# MCU.net
KiCad netlist of a schematic drawn in Altium Designer
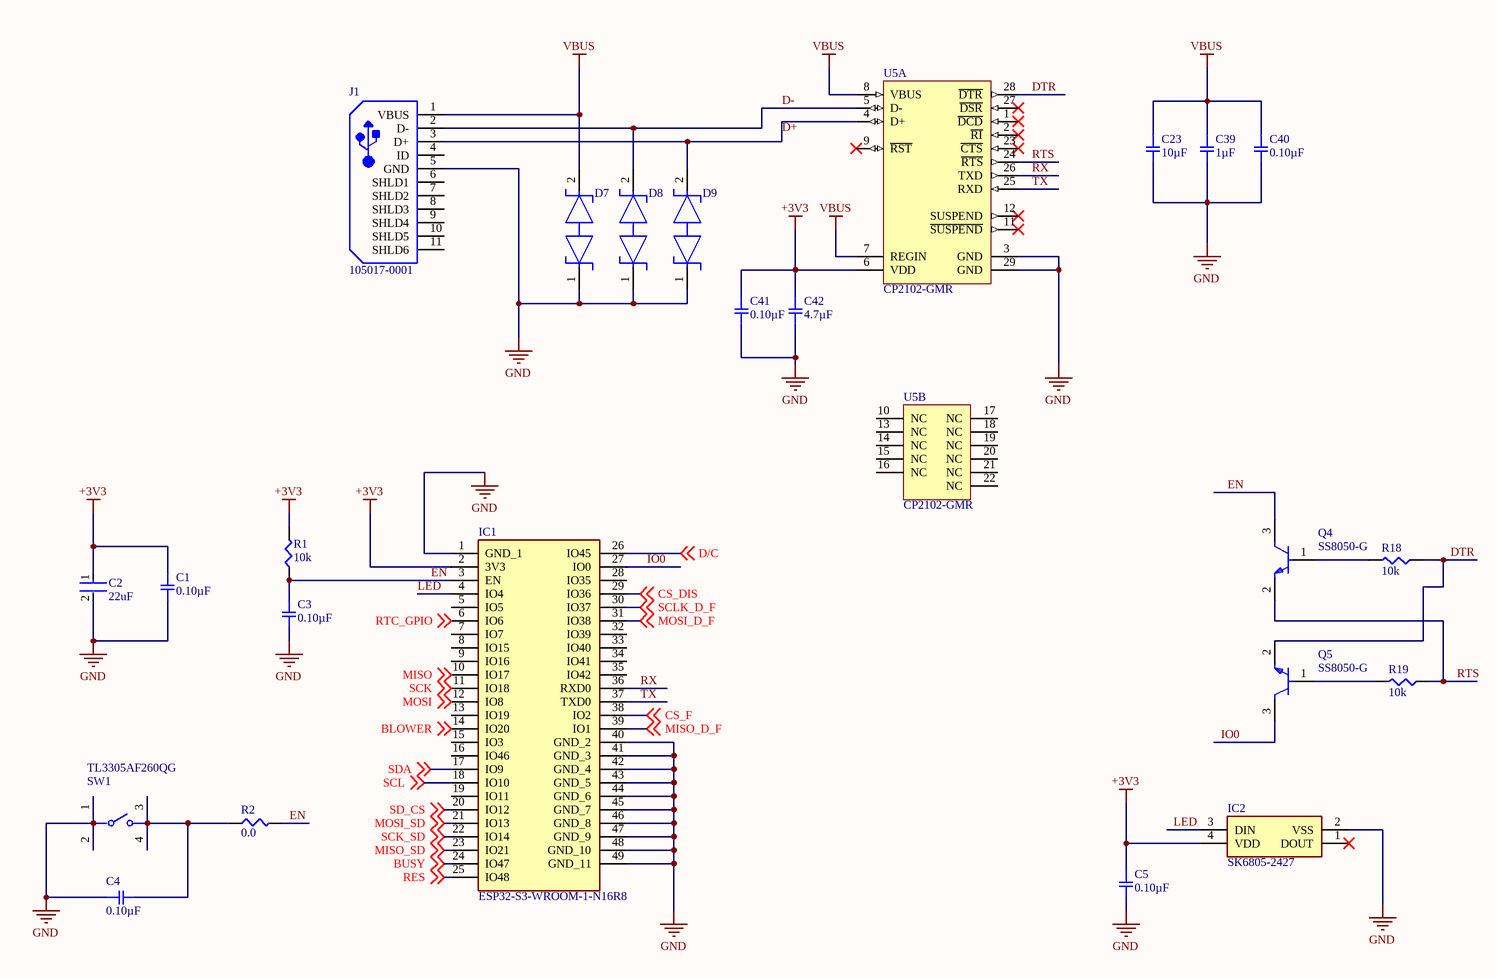
[diagram p0: MCU.SchDoc]

(export (version "E")
  (design (tool "Eeschema 10.0.6"))
  (components
    (comp (ref "C1")
      (value "0.10µF")
      (footprint "SMD-0402C")
      (description "CAP CER 0.1UF 16V X7R 0402")
      (fields
        (field (name "DIGI-KEY PART NUMBER") "490-4759-1-ND")
        (field (name "PART NUMBER") "GCM155R71C104KA55D")
      )
      (libsource (lib "capacitor_murata_0402") (part "GCM155R71C104KA55D"))
    )
    (comp (ref "C2")
      (value "22uF")
      (footprint "FP-CL05A226MQ5N6J8-IPC_C")
      (description "CAP CER 22UF 6.3V X5R 0402")
      (fields
        (field (name "MANUFACTURER PART NUMBER") "CL05A226MQ5N6J8")
        (field (name "MANUFACTURER") "Samsung Electro-Mechanics")
      )
      (libsource (lib "Altium Content Vault") (part "11868f565c42a9108669ba33697ecf6"))
    )
    (comp (ref "C3")
      (value "0.10µF")
      (footprint "SMD-0402C")
      (description "CAP CER 0.1UF 16V X7R 0402")
      (fields
        (field (name "DIGI-KEY PART NUMBER") "490-4759-1-ND")
        (field (name "PART NUMBER") "GCM155R71C104KA55D")
      )
      (libsource (lib "capacitor_murata_0402") (part "GCM155R71C104KA55D"))
    )
    (comp (ref "C4")
      (value "0.10µF")
      (footprint "SMD-0402C")
      (description "CAP CER 0.1UF 16V X7R 0402")
      (fields
        (field (name "DIGI-KEY PART NUMBER") "490-4759-1-ND")
        (field (name "PART NUMBER") "GCM155R71C104KA55D")
      )
      (libsource (lib "capacitor_murata_0402") (part "GCM155R71C104KA55D"))
    )
    (comp (ref "C5")
      (value "0.10µF")
      (footprint "SMD-0402C")
      (description "CAP CER 0.1UF 16V X7R 0402")
      (fields
        (field (name "DIGI-KEY PART NUMBER") "490-4759-1-ND")
        (field (name "PART NUMBER") "GCM155R71C104KA55D")
      )
      (libsource (lib "capacitor_murata_0402") (part "GCM155R71C104KA55D"))
    )
    (comp (ref "C23")
      (value "10µF")
      (footprint "SMD-0402C")
      (description "CAP CER 10UF 6.3V X5R 0402")
      (fields
        (field (name "DIGI-KEY PART NUMBER") "490-13251-1-ND")
        (field (name "PART NUMBER") "ZRB15XR60J106ME12D")
      )
      (libsource (lib "capacitor_murata_0402") (part "ZRB15XR60J106ME12D"))
    )
    (comp (ref "C39")
      (value "1µF")
      (footprint "SMD-0402C")
      (description "CAP CER 1UF 10V X7S 0402")
      (fields
        (field (name "DIGI-KEY PART NUMBER") "490-13409-1-ND")
        (field (name "PART NUMBER") "GCM155C71A105KE38D")
      )
      (libsource (lib "capacitor_murata_0402") (part "GCM155C71A105KE38D"))
    )
    (comp (ref "C40")
      (value "0.10µF")
      (footprint "SMD-0402C")
      (description "CAP CER 0.1UF 16V X7R 0402")
      (fields
        (field (name "DIGI-KEY PART NUMBER") "490-4759-1-ND")
        (field (name "PART NUMBER") "GCM155R71C104KA55D")
      )
      (libsource (lib "capacitor_murata_0402") (part "GCM155R71C104KA55D"))
    )
    (comp (ref "C41")
      (value "0.10µF")
      (footprint "SMD-0402C")
      (description "CAP CER 0.1UF 16V X7R 0402")
      (fields
        (field (name "DIGI-KEY PART NUMBER") "490-4759-1-ND")
        (field (name "PART NUMBER") "GCM155R71C104KA55D")
      )
      (libsource (lib "capacitor_murata_0402") (part "GCM155R71C104KA55D"))
    )
    (comp (ref "C42")
      (value "4.7µF")
      (footprint "SMD-0402C")
      (description "CAP CER 4.7UF 10V X5R 0402")
      (fields
        (field (name "DIGI-KEY PART NUMBER") "490-13252-1-ND")
        (field (name "PART NUMBER") "ZRB15XR61A475KE01D")
      )
      (libsource (lib "capacitor_murata_0402") (part "ZRB15XR61A475KE01D"))
    )
    (comp (ref "D7")
      (value "PD1E10B06DPYR")
      (footprint "FP-DPY0002A-MFG")
      (description "TVS DIODE 5.5V 14V 2X1SON")
      (libsource (lib "Altium Content Vault") (part "208e19b57522434895fa003e5d5b197"))
    )
    (comp (ref "D8")
      (value "PD1E10B06DPYR")
      (footprint "FP-DPY0002A-MFG")
      (description "TVS DIODE 5.5V 14V 2X1SON")
      (libsource (lib "Altium Content Vault") (part "208e19b57522434895fa003e5d5b197"))
    )
    (comp (ref "D9")
      (value "PD1E10B06DPYR")
      (footprint "FP-DPY0002A-MFG")
      (description "TVS DIODE 5.5V 14V 2X1SON")
      (libsource (lib "Altium Content Vault") (part "208e19b57522434895fa003e5d5b197"))
    )
    (comp (ref "IC1")
      (value "ESP32-S3-WROOM-1-N16R8")
      (footprint "SamacSys:ESP32S3WROOM1N16R8")
      (description "Integrated Circuit")
      (fields (field (name "MOUSER PART NUMBER") "356-ESP32S3WRM1N16R8"))
      (libsource (lib "SamacSys") (part "ESP32-S3-WROOM-1-N16R8"))
    )
    (comp (ref "IC2")
      (value "SK6805-2427")
      (footprint "SamacSys:SK68052427")
      (description "Integrated Circuit")
      (libsource (lib "*") (part "SK6805-2427"))
    )
    (comp (ref "J1")
      (value "105017-0001")
      (footprint "USB-MICRO-B_V")
      (fields (field (name "MANUFACTURER") "Molex"))
      (libsource (lib "Altium Content Vault") (part "USB-5-6SHLD"))
    )
    (comp (ref "Q4")
      (value "SS8050-G")
      (footprint "FP-SS8050-G-MFG")
      (description "NPN TRANSISTOR 1.5A 40V SOT-23 R")
      (libsource (lib "Altium Content Vault") (part "2a1388f82443b098dcd57d24ac7632d"))
    )
    (comp (ref "Q5")
      (value "SS8050-G")
      (footprint "FP-SS8050-G-MFG")
      (description "NPN TRANSISTOR 1.5A 40V SOT-23 R")
      (libsource (lib "Altium Content Vault") (part "2a1388f82443b098dcd57d24ac7632d"))
    )
    (comp (ref "R1")
      (value "10k")
      (footprint "SMD-0402-RES")
      (description "RES SMD 10K OHM 5% 1/10W 0402")
      (fields (field (name "PART NUMBER") "ERJ-2GEJ103X") (field (name "DIGI-KEY PART NUMBER") "P10KJCT-ND"))
      (libsource (lib "Panasonic_ERJ_0402") (part "ERJ-2GEJ103X"))
    )
    (comp (ref "R2")
      (value "0.0")
      (footprint "SMD-0402-RES")
      (description "RES SMD 0.0OHM JUMPER 1/10W 0402")
      (fields (field (name "PART NUMBER") "ERJ-2GE0R00X") (field (name "DIGI-KEY PART NUMBER") "P0.0JCT-ND"))
      (libsource (lib "Panasonic_ERJ_0402") (part "ERJ-2GE0R00X"))
    )
    (comp (ref "R18")
      (value "10k")
      (footprint "SMD-0402-RES")
      (description "RES SMD 10K OHM 5% 1/10W 0402")
      (fields (field (name "PART NUMBER") "ERJ-2GEJ103X") (field (name "DIGI-KEY PART NUMBER") "P10KJCT-ND"))
      (libsource (lib "Panasonic_ERJ_0402") (part "ERJ-2GEJ103X"))
    )
    (comp (ref "R19")
      (value "10k")
      (footprint "SMD-0402-RES")
      (description "RES SMD 10K OHM 5% 1/10W 0402")
      (fields (field (name "PART NUMBER") "ERJ-2GEJ103X") (field (name "DIGI-KEY PART NUMBER") "P10KJCT-ND"))
      (libsource (lib "Panasonic_ERJ_0402") (part "ERJ-2GEJ103X"))
    )
    (comp (ref "SW1")
      (value "TL3305AF260QG")
      (footprint "FP-TL3305AF260QG-MFG")
      (description "SWITCH TACTILE SPST-NO 50MA 12V")
      (libsource (lib "Altium Content Vault") (part "b8895f3f4cefb76e1819d2863dba89b"))
    )
    (comp (ref "U5")
      (value "CP2102-GMR")
      (footprint "SLAB-QFN-28-3125x3125TP_M")
      (description "Single-Chip USB to URAT Bridge, 3.3 V, -40 to 85 degC, 28-Pin QFN, RoHS, Tape and Reel")
      (fields (field (name "MANUFACTURER") "Silicon Labs"))
      (libsource (lib "Altium Content Vault") (part "SLAB-CP210X-QFN-28-29"))
    )
  )
  (nets
    (net (code "1") (name "+3V3") (class "Default")
      (node (ref "C1") (pin "1") (pinfunction "1_1") (pintype "passive"))
      (node (ref "C2") (pin "1") (pinfunction "1_1") (pintype "passive"))
      (node (ref "C41") (pin "1") (pinfunction "1_1") (pintype "passive"))
      (node (ref "C42") (pin "1") (pinfunction "1_1") (pintype "passive"))
      (node (ref "C5") (pin "1") (pinfunction "1_1") (pintype "passive"))
      (node (ref "IC1") (pin "2") (pinfunction "3V3_2") (pintype "passive"))
      (node (ref "IC2") (pin "4") (pinfunction "VDD_4") (pintype "passive"))
      (node (ref "R1") (pin "2") (pinfunction "2_2") (pintype "passive"))
      (node (ref "U5") (pin "6") (pinfunction "VDD_6") (pintype "power_in"))
    )
    (net (code "2") (name "/D+") (class "Default")
      (node (ref "D9") (pin "2") (pinfunction "2_2") (pintype "passive"))
      (node (ref "J1") (pin "3") (pinfunction "D+_3") (pintype "passive"))
      (node (ref "U5") (pin "4") (pinfunction "D+_4") (pintype "bidirectional"))
    )
    (net (code "3") (name "/D-") (class "Default")
      (node (ref "D8") (pin "2") (pinfunction "2_2") (pintype "passive"))
      (node (ref "J1") (pin "2") (pinfunction "D-_2") (pintype "passive"))
      (node (ref "U5") (pin "5") (pinfunction "D-_5") (pintype "bidirectional"))
    )
    (net (code "4") (name "/DTR") (class "Default")
      (node (ref "Q5") (pin "2") (pinfunction "E_2") (pintype "passive"))
      (node (ref "R18") (pin "1") (pinfunction "1_1") (pintype "passive"))
      (node (ref "U5") (pin "28") (pinfunction "~{DTR}_28") (pintype "output"))
    )
    (net (code "5") (name "/EN") (class "Default")
      (node (ref "C3") (pin "1") (pinfunction "1_1") (pintype "passive"))
      (node (ref "IC1") (pin "3") (pinfunction "EN_3") (pintype "passive"))
      (node (ref "Q4") (pin "3") (pinfunction "C_3") (pintype "passive"))
      (node (ref "R1") (pin "1") (pinfunction "1_1") (pintype "passive"))
      (node (ref "R2") (pin "2") (pinfunction "2_2") (pintype "passive"))
    )
    (net (code "6") (name "/IO0") (class "Default")
      (node (ref "IC1") (pin "27") (pinfunction "IO0_27") (pintype "passive"))
      (node (ref "Q5") (pin "3") (pinfunction "C_3") (pintype "passive"))
    )
    (net (code "7") (name "/LED") (class "Default")
      (node (ref "IC1") (pin "4") (pinfunction "IO4_4") (pintype "passive"))
      (node (ref "IC2") (pin "3") (pinfunction "DIN_3") (pintype "passive"))
    )
    (net (code "8") (name "/RTS") (class "Default")
      (node (ref "Q4") (pin "2") (pinfunction "E_2") (pintype "passive"))
      (node (ref "R19") (pin "1") (pinfunction "1_1") (pintype "passive"))
      (node (ref "U5") (pin "24") (pinfunction "~{RTS}_24") (pintype "output"))
    )
    (net (code "9") (name "/RX") (class "Default")
      (node (ref "IC1") (pin "36") (pinfunction "RXD0_36") (pintype "passive"))
      (node (ref "U5") (pin "26") (pinfunction "TXD_26") (pintype "output"))
    )
    (net (code "10") (name "/TX") (class "Default")
      (node (ref "IC1") (pin "37") (pinfunction "TXD0_37") (pintype "passive"))
      (node (ref "U5") (pin "25") (pinfunction "RXD_25") (pintype "input"))
    )
    (net (code "11") (name "BLOWER") (class "Default")
      (node (ref "IC1") (pin "14") (pinfunction "IO20_14") (pintype "passive"))
    )
    (net (code "12") (name "BUSY") (class "Default")
      (node (ref "IC1") (pin "24") (pinfunction "IO47_24") (pintype "passive"))
    )
    (net (code "13") (name "CS_DIS") (class "Default")
      (node (ref "IC1") (pin "29") (pinfunction "IO36_29") (pintype "passive"))
    )
    (net (code "14") (name "CS_F") (class "Default")
      (node (ref "IC1") (pin "38") (pinfunction "IO2_38") (pintype "passive"))
    )
    (net (code "15") (name "D{slash}C") (class "Default")
      (node (ref "IC1") (pin "26") (pinfunction "IO45_26") (pintype "passive"))
    )
    (net (code "16") (name "GND") (class "Default")
      (node (ref "C1") (pin "2") (pinfunction "2_2") (pintype "passive"))
      (node (ref "C2") (pin "2") (pinfunction "2_2") (pintype "passive"))
      (node (ref "C23") (pin "2") (pinfunction "2_2") (pintype "passive"))
      (node (ref "C3") (pin "2") (pinfunction "2_2") (pintype "passive"))
      (node (ref "C39") (pin "2") (pinfunction "2_2") (pintype "passive"))
      (node (ref "C4") (pin "1") (pinfunction "1_1") (pintype "passive"))
      (node (ref "C40") (pin "2") (pinfunction "2_2") (pintype "passive"))
      (node (ref "C41") (pin "2") (pinfunction "2_2") (pintype "passive"))
      (node (ref "C42") (pin "2") (pinfunction "2_2") (pintype "passive"))
      (node (ref "C5") (pin "2") (pinfunction "2_2") (pintype "passive"))
      (node (ref "D7") (pin "1") (pinfunction "1_1") (pintype "passive"))
      (node (ref "D8") (pin "1") (pinfunction "1_1") (pintype "passive"))
      (node (ref "D9") (pin "1") (pinfunction "1_1") (pintype "passive"))
      (node (ref "IC1") (pin "1") (pinfunction "GND_1_1") (pintype "passive"))
      (node (ref "IC1") (pin "40") (pinfunction "GND_2_40") (pintype "passive"))
      (node (ref "IC1") (pin "41") (pinfunction "GND_3_41") (pintype "passive"))
      (node (ref "IC1") (pin "42") (pinfunction "GND_4_42") (pintype "passive"))
      (node (ref "IC1") (pin "43") (pinfunction "GND_5_43") (pintype "passive"))
      (node (ref "IC1") (pin "44") (pinfunction "GND_6_44") (pintype "passive"))
      (node (ref "IC1") (pin "45") (pinfunction "GND_7_45") (pintype "passive"))
      (node (ref "IC1") (pin "46") (pinfunction "GND_8_46") (pintype "passive"))
      (node (ref "IC1") (pin "47") (pinfunction "GND_9_47") (pintype "passive"))
      (node (ref "IC1") (pin "48") (pinfunction "GND_10_48") (pintype "passive"))
      (node (ref "IC1") (pin "49") (pinfunction "GND_11_49") (pintype "passive"))
      (node (ref "IC2") (pin "2") (pinfunction "VSS_2") (pintype "passive"))
      (node (ref "J1") (pin "5") (pinfunction "GND_5") (pintype "passive"))
      (node (ref "SW1") (pin "1") (pinfunction "1_1") (pintype "passive"))
      (node (ref "SW1") (pin "2") (pinfunction "2_2") (pintype "passive"))
      (node (ref "U5") (pin "29") (pinfunction "GND_29") (pintype "power_in"))
      (node (ref "U5") (pin "3") (pinfunction "GND_3") (pintype "power_in"))
    )
    (net (code "17") (name "MISO") (class "Default")
      (node (ref "IC1") (pin "10") (pinfunction "IO17_10") (pintype "passive"))
    )
    (net (code "18") (name "MISO_D_F") (class "Default")
      (node (ref "IC1") (pin "39") (pinfunction "IO1_39") (pintype "passive"))
    )
    (net (code "19") (name "MISO_SD") (class "Default")
      (node (ref "IC1") (pin "23") (pinfunction "IO21_23") (pintype "passive"))
    )
    (net (code "20") (name "MOSI") (class "Default")
      (node (ref "IC1") (pin "12") (pinfunction "IO8_12") (pintype "passive"))
    )
    (net (code "21") (name "MOSI_D_F") (class "Default")
      (node (ref "IC1") (pin "31") (pinfunction "IO38_31") (pintype "passive"))
    )
    (net (code "22") (name "MOSI_SD") (class "Default")
      (node (ref "IC1") (pin "21") (pinfunction "IO13_21") (pintype "passive"))
    )
    (net (code "23") (name "Net-(C4-Pad2)") (class "Default")
      (node (ref "C4") (pin "2") (pinfunction "2_2") (pintype "passive"))
      (node (ref "R2") (pin "1") (pinfunction "1_1") (pintype "passive"))
      (node (ref "SW1") (pin "3") (pinfunction "3_3") (pintype "passive"))
      (node (ref "SW1") (pin "4") (pinfunction "4_4") (pintype "passive"))
    )
    (net (code "24") (name "Net-(Q4-B)") (class "Default")
      (node (ref "Q4") (pin "1") (pinfunction "B_1") (pintype "passive"))
      (node (ref "R18") (pin "2") (pinfunction "2_2") (pintype "passive"))
    )
    (net (code "25") (name "Net-(Q5-B)") (class "Default")
      (node (ref "Q5") (pin "1") (pinfunction "B_1") (pintype "passive"))
      (node (ref "R19") (pin "2") (pinfunction "2_2") (pintype "passive"))
    )
    (net (code "26") (name "RES") (class "Default")
      (node (ref "IC1") (pin "25") (pinfunction "IO48_25") (pintype "passive"))
    )
    (net (code "27") (name "RTC_GPIO") (class "Default")
      (node (ref "IC1") (pin "6") (pinfunction "IO6_6") (pintype "passive"))
    )
    (net (code "28") (name "SCK") (class "Default")
      (node (ref "IC1") (pin "11") (pinfunction "IO18_11") (pintype "passive"))
    )
    (net (code "29") (name "SCK_SD") (class "Default")
      (node (ref "IC1") (pin "22") (pinfunction "IO14_22") (pintype "passive"))
    )
    (net (code "30") (name "SCL") (class "Default")
      (node (ref "IC1") (pin "18") (pinfunction "IO10_18") (pintype "passive"))
    )
    (net (code "31") (name "SCLK_D_F") (class "Default")
      (node (ref "IC1") (pin "30") (pinfunction "IO37_30") (pintype "passive"))
    )
    (net (code "32") (name "SDA") (class "Default")
      (node (ref "IC1") (pin "17") (pinfunction "IO9_17") (pintype "passive"))
    )
    (net (code "33") (name "SD_CS") (class "Default")
      (node (ref "IC1") (pin "20") (pinfunction "IO12_20") (pintype "passive"))
    )
    (net (code "34") (name "VBUS") (class "Default")
      (node (ref "C23") (pin "1") (pinfunction "1_1") (pintype "passive"))
      (node (ref "C39") (pin "1") (pinfunction "1_1") (pintype "passive"))
      (node (ref "C40") (pin "1") (pinfunction "1_1") (pintype "passive"))
      (node (ref "D7") (pin "2") (pinfunction "2_2") (pintype "passive"))
      (node (ref "J1") (pin "1") (pinfunction "VBUS_1") (pintype "passive"))
      (node (ref "U5") (pin "7") (pinfunction "REGIN_7") (pintype "power_in"))
      (node (ref "U5") (pin "8") (pinfunction "VBUS_8") (pintype "input"))
    )
    (net (code "35") (name "unconnected-(IC1-IO3-Pad15)") (class "Default")
      (node (ref "IC1") (pin "15") (pinfunction "IO3_15") (pintype "passive"))
    )
    (net (code "36") (name "unconnected-(IC1-IO5-Pad5)") (class "Default")
      (node (ref "IC1") (pin "5") (pinfunction "IO5_5") (pintype "passive"))
    )
    (net (code "37") (name "unconnected-(IC1-IO7-Pad7)") (class "Default")
      (node (ref "IC1") (pin "7") (pinfunction "IO7_7") (pintype "passive"))
    )
    (net (code "38") (name "unconnected-(IC1-IO11-Pad19)") (class "Default")
      (node (ref "IC1") (pin "19") (pinfunction "IO11_19") (pintype "passive"))
    )
    (net (code "39") (name "unconnected-(IC1-IO15-Pad8)") (class "Default")
      (node (ref "IC1") (pin "8") (pinfunction "IO15_8") (pintype "passive"))
    )
    (net (code "40") (name "unconnected-(IC1-IO16-Pad9)") (class "Default")
      (node (ref "IC1") (pin "9") (pinfunction "IO16_9") (pintype "passive"))
    )
    (net (code "41") (name "unconnected-(IC1-IO19-Pad13)") (class "Default")
      (node (ref "IC1") (pin "13") (pinfunction "IO19_13") (pintype "passive"))
    )
    (net (code "42") (name "unconnected-(IC1-IO35-Pad28)") (class "Default")
      (node (ref "IC1") (pin "28") (pinfunction "IO35_28") (pintype "passive"))
    )
    (net (code "43") (name "unconnected-(IC1-IO39-Pad32)") (class "Default")
      (node (ref "IC1") (pin "32") (pinfunction "IO39_32") (pintype "passive"))
    )
    (net (code "44") (name "unconnected-(IC1-IO40-Pad33)") (class "Default")
      (node (ref "IC1") (pin "33") (pinfunction "IO40_33") (pintype "passive"))
    )
    (net (code "45") (name "unconnected-(IC1-IO41-Pad34)") (class "Default")
      (node (ref "IC1") (pin "34") (pinfunction "IO41_34") (pintype "passive"))
    )
    (net (code "46") (name "unconnected-(IC1-IO42-Pad35)") (class "Default")
      (node (ref "IC1") (pin "35") (pinfunction "IO42_35") (pintype "passive"))
    )
    (net (code "47") (name "unconnected-(IC1-IO46-Pad16)") (class "Default")
      (node (ref "IC1") (pin "16") (pinfunction "IO46_16") (pintype "passive"))
    )
    (net (code "48") (name "unconnected-(IC2-DOUT-Pad1)") (class "Default")
      (node (ref "IC2") (pin "1") (pinfunction "DOUT_1") (pintype "passive+no_connect"))
    )
    (net (code "49") (name "unconnected-(J1-ID-Pad4)") (class "Default")
      (node (ref "J1") (pin "4") (pinfunction "ID_4") (pintype "passive"))
    )
    (net (code "50") (name "unconnected-(J1-SHLD1-Pad6)") (class "Default")
      (node (ref "J1") (pin "6") (pinfunction "SHLD1_6") (pintype "passive"))
    )
    (net (code "51") (name "unconnected-(J1-SHLD2-Pad7)") (class "Default")
      (node (ref "J1") (pin "7") (pinfunction "SHLD2_7") (pintype "passive"))
    )
    (net (code "52") (name "unconnected-(J1-SHLD3-Pad8)") (class "Default")
      (node (ref "J1") (pin "8") (pinfunction "SHLD3_8") (pintype "passive"))
    )
    (net (code "53") (name "unconnected-(J1-SHLD4-Pad9)") (class "Default")
      (node (ref "J1") (pin "9") (pinfunction "SHLD4_9") (pintype "passive"))
    )
    (net (code "54") (name "unconnected-(J1-SHLD5-Pad10)") (class "Default")
      (node (ref "J1") (pin "10") (pinfunction "SHLD5_10") (pintype "passive"))
    )
    (net (code "55") (name "unconnected-(J1-SHLD6-Pad11)") (class "Default")
      (node (ref "J1") (pin "11") (pinfunction "SHLD6_11") (pintype "passive"))
    )
    (net (code "56") (name "unconnected-(U5A-SUSPEND-Pad12)") (class "Default")
      (node (ref "U5") (pin "12") (pinfunction "SUSPEND_12") (pintype "output+no_connect"))
    )
    (net (code "57") (name "unconnected-(U5A-~{CTS}-Pad23)") (class "Default")
      (node (ref "U5") (pin "23") (pinfunction "~{CTS}_23") (pintype "input+no_connect"))
    )
    (net (code "58") (name "unconnected-(U5A-~{DCD}-Pad1)") (class "Default")
      (node (ref "U5") (pin "1") (pinfunction "~{DCD}_1") (pintype "input+no_connect"))
    )
    (net (code "59") (name "unconnected-(U5A-~{DSR}-Pad27)") (class "Default")
      (node (ref "U5") (pin "27") (pinfunction "~{DSR}_27") (pintype "input+no_connect"))
    )
    (net (code "60") (name "unconnected-(U5A-~{RI}-Pad2)") (class "Default")
      (node (ref "U5") (pin "2") (pinfunction "~{RI}_2") (pintype "input+no_connect"))
    )
    (net (code "61") (name "unconnected-(U5A-~{RST}-Pad9)") (class "Default")
      (node (ref "U5") (pin "9") (pinfunction "~{RST}_9") (pintype "bidirectional+no_connect"))
    )
    (net (code "62") (name "unconnected-(U5A-~{SUSPEND}-Pad11)") (class "Default")
      (node (ref "U5") (pin "11") (pinfunction "~{SUSPEND}_11") (pintype "output+no_connect"))
    )
    (net (code "63") (name "unconnected-(U5B-NC-Pad10)") (class "Default")
      (node (ref "U5") (pin "10") (pinfunction "NC_10") (pintype "passive"))
    )
    (net (code "64") (name "unconnected-(U5B-NC-Pad13)") (class "Default")
      (node (ref "U5") (pin "13") (pinfunction "NC_13") (pintype "passive"))
    )
    (net (code "65") (name "unconnected-(U5B-NC-Pad14)") (class "Default")
      (node (ref "U5") (pin "14") (pinfunction "NC_14") (pintype "passive"))
    )
    (net (code "66") (name "unconnected-(U5B-NC-Pad15)") (class "Default")
      (node (ref "U5") (pin "15") (pinfunction "NC_15") (pintype "passive"))
    )
    (net (code "67") (name "unconnected-(U5B-NC-Pad16)") (class "Default")
      (node (ref "U5") (pin "16") (pinfunction "NC_16") (pintype "passive"))
    )
    (net (code "68") (name "unconnected-(U5B-NC-Pad17)") (class "Default")
      (node (ref "U5") (pin "17") (pinfunction "NC_17") (pintype "passive"))
    )
    (net (code "69") (name "unconnected-(U5B-NC-Pad18)") (class "Default")
      (node (ref "U5") (pin "18") (pinfunction "NC_18") (pintype "passive"))
    )
    (net (code "70") (name "unconnected-(U5B-NC-Pad19)") (class "Default")
      (node (ref "U5") (pin "19") (pinfunction "NC_19") (pintype "passive"))
    )
    (net (code "71") (name "unconnected-(U5B-NC-Pad20)") (class "Default")
      (node (ref "U5") (pin "20") (pinfunction "NC_20") (pintype "passive"))
    )
    (net (code "72") (name "unconnected-(U5B-NC-Pad21)") (class "Default")
      (node (ref "U5") (pin "21") (pinfunction "NC_21") (pintype "passive"))
    )
    (net (code "73") (name "unconnected-(U5B-NC-Pad22)") (class "Default")
      (node (ref "U5") (pin "22") (pinfunction "NC_22") (pintype "passive"))
    )
  )
)
